# Balancing_Robot_1_1_Sensors.net
KiCad netlist of a schematic drawn in Altium Designer
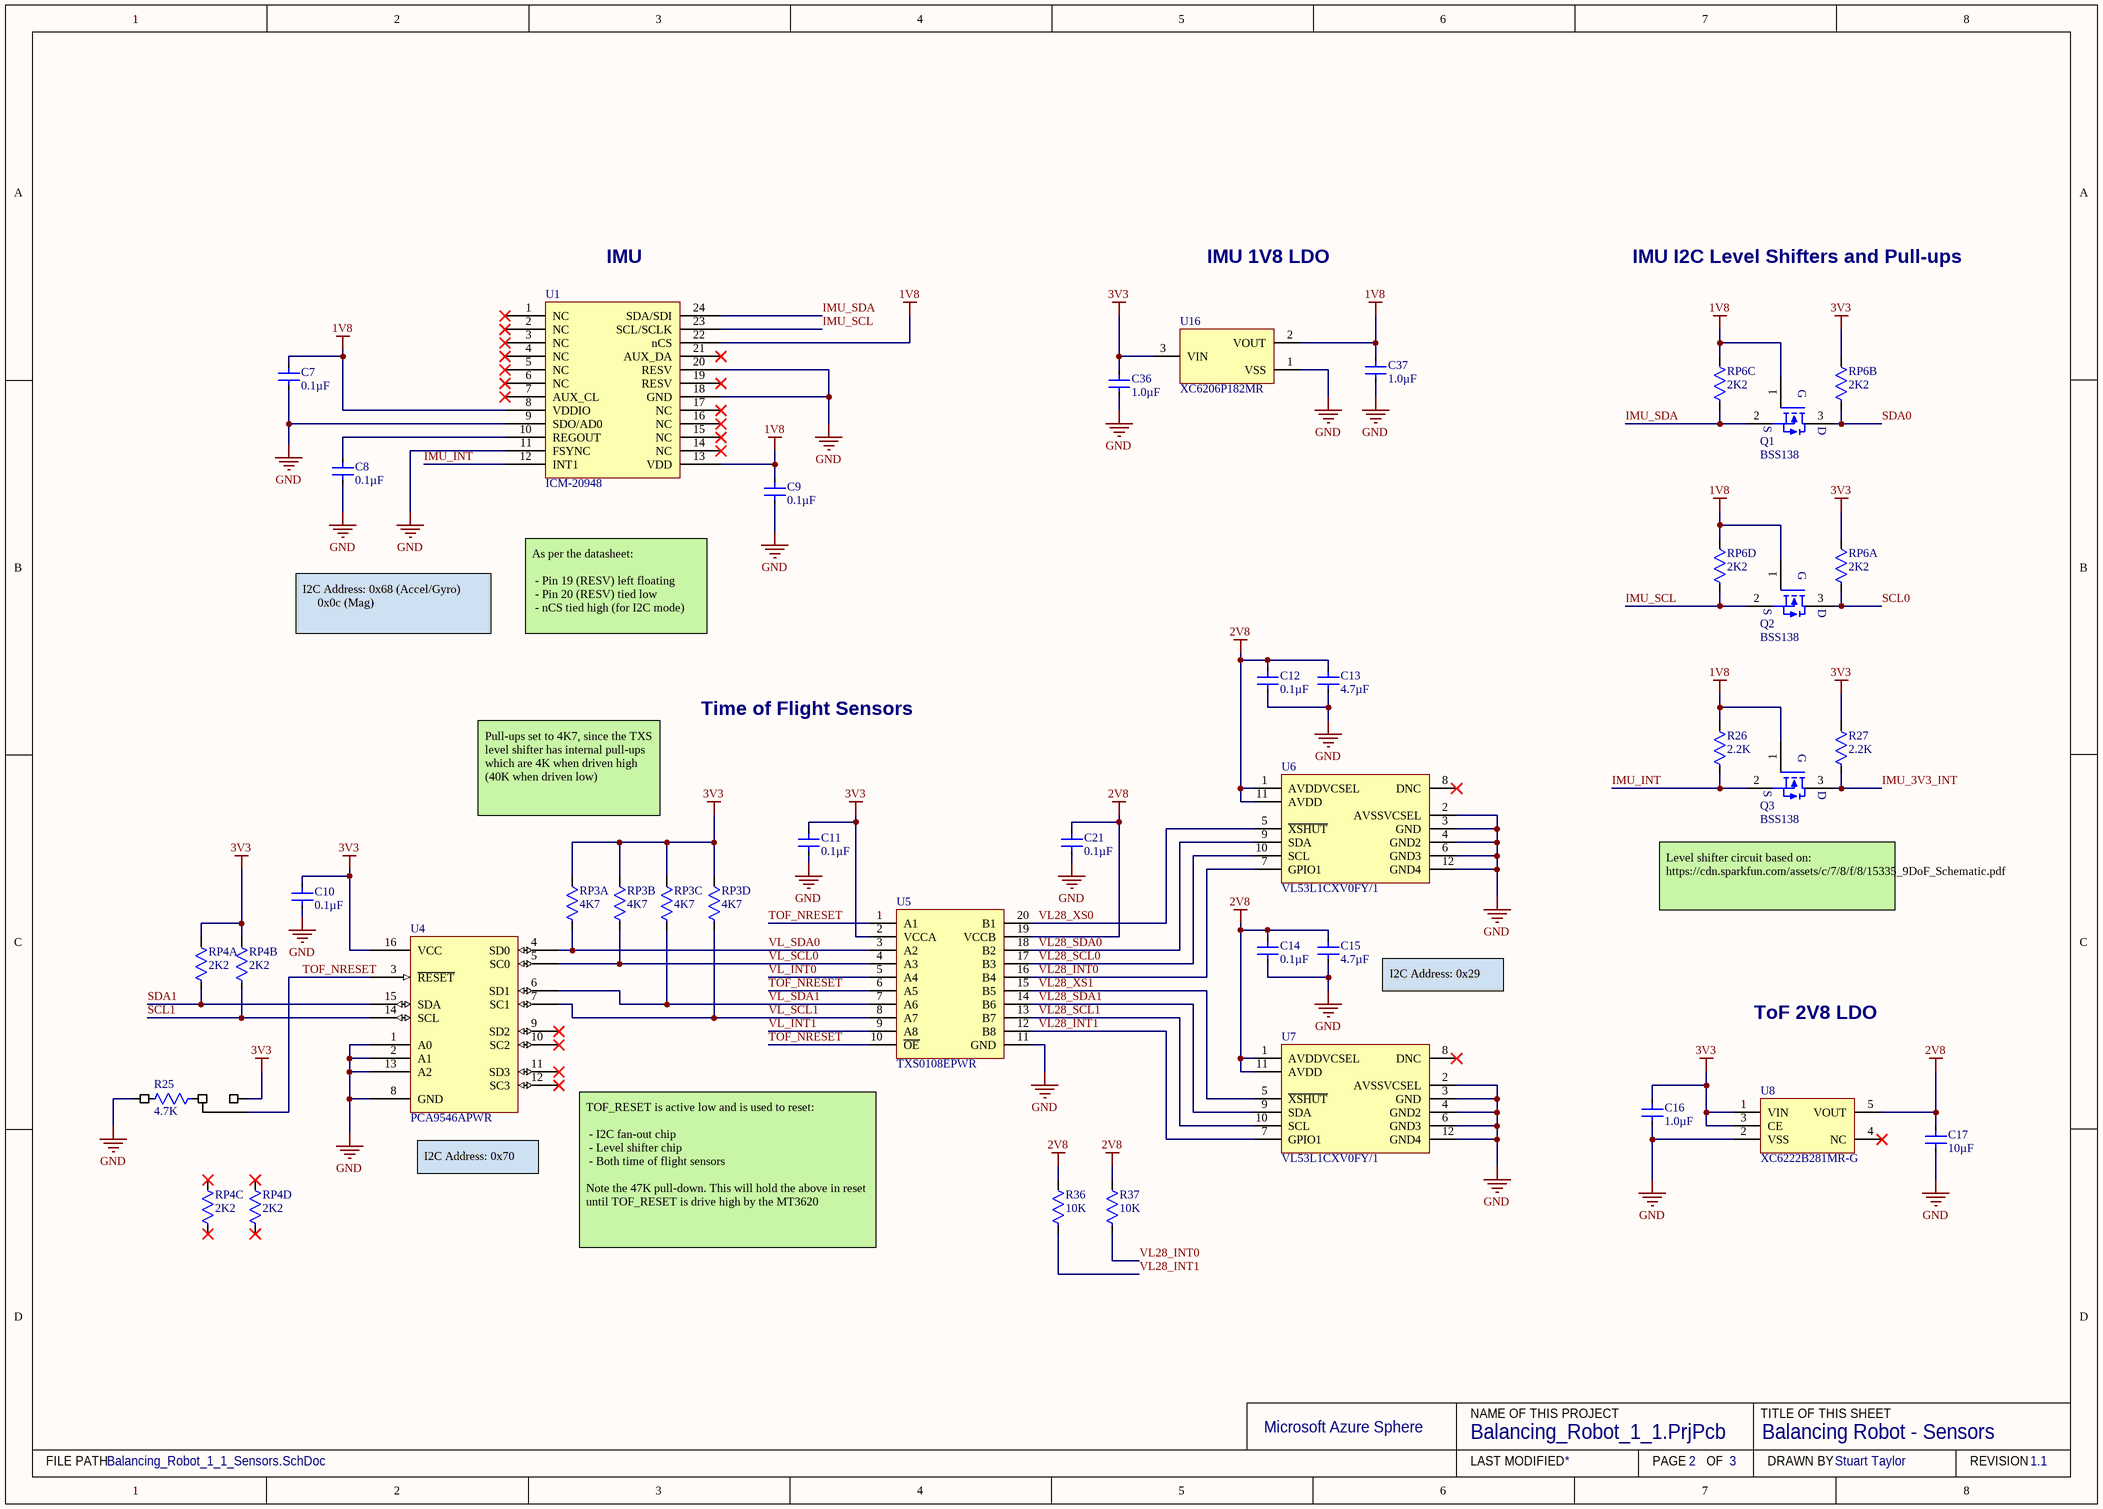
[diagram p0: Balancing_Robot_1_1_Sensors.SchDoc]

(export (version "E")
  (design (tool "Eeschema 10.0.6"))
  (components
    (comp (ref "C7")
      (value "0.1µF")
      (footprint "CAPC1005-EIA0402 0.55MM MED")
      (description "CAP CER 0.1UF 50V 10% X7R 0402")
      (fields
        (field (name "MANUFACTURER") "TDK Corporation")
        (field (name "MANUFACTURER PART NUMBER") "C1005X7R1H104K050BB")
        (field (name "CAPACITANCE") "0.1µF")
      )
      (libsource (lib "TDK_Capacitor_C_0402") (part "0.1µF 0402 X7R 50V"))
    )
    (comp (ref "C8")
      (value "0.1µF")
      (footprint "CAPC1005-EIA0402 0.55MM MED")
      (description "CAP CER 0.1UF 50V 10% X7R 0402")
      (fields
        (field (name "MANUFACTURER") "TDK Corporation")
        (field (name "MANUFACTURER PART NUMBER") "C1005X7R1H104K050BB")
        (field (name "CAPACITANCE") "0.1µF")
      )
      (libsource (lib "TDK_Capacitor_C_0402") (part "0.1µF 0402 X7R 50V"))
    )
    (comp (ref "C9")
      (value "0.1µF")
      (footprint "CAPC1005-EIA0402 0.55MM MED")
      (description "CAP CER 0.1UF 50V 10% X7R 0402")
      (fields
        (field (name "MANUFACTURER") "TDK Corporation")
        (field (name "MANUFACTURER PART NUMBER") "C1005X7R1H104K050BB")
        (field (name "CAPACITANCE") "0.1µF")
      )
      (libsource (lib "TDK_Capacitor_C_0402") (part "0.1µF 0402 X7R 50V"))
    )
    (comp (ref "C10")
      (value "0.1µF")
      (footprint "CAPC1005-EIA0402 0.55MM MED")
      (description "CAP CER 0.1UF 50V 10% X7R 0402")
      (fields
        (field (name "MANUFACTURER") "TDK Corporation")
        (field (name "MANUFACTURER PART NUMBER") "C1005X7R1H104K050BB")
        (field (name "CAPACITANCE") "0.1µF")
      )
      (libsource (lib "TDK_Capacitor_C_0402") (part "0.1µF 0402 X7R 50V"))
    )
    (comp (ref "C11")
      (value "0.1µF")
      (footprint "CAPC1005-EIA0402 0.55MM MED")
      (description "CAP CER 0.1UF 50V 10% X7R 0402")
      (fields
        (field (name "MANUFACTURER") "TDK Corporation")
        (field (name "MANUFACTURER PART NUMBER") "C1005X7R1H104K050BB")
        (field (name "CAPACITANCE") "0.1µF")
      )
      (libsource (lib "TDK_Capacitor_C_0402") (part "0.1µF 0402 X7R 50V"))
    )
    (comp (ref "C12")
      (value "0.1µF")
      (footprint "CAPC1005-EIA0402 0.55MM MED")
      (description "CAP CER 0.1UF 50V 10% X7R 0402")
      (fields
        (field (name "MANUFACTURER") "TDK Corporation")
        (field (name "MANUFACTURER PART NUMBER") "C1005X7R1H104K050BB")
        (field (name "CAPACITANCE") "0.1µF")
      )
      (libsource (lib "TDK_Capacitor_C_0402") (part "0.1µF 0402 X7R 50V"))
    )
    (comp (ref "C13")
      (value "C1005X5R1A475K050BC")
      (footprint "CAPC1005-EIA0402 0.55MM MED")
      (description "CAP CER 4.7UF 10V 10% X5R 0402")
      (fields
        (field (name "MANUFACTURER") "TDK Corporation")
        (field (name "TOLERANCE") "±10%")
        (field (name "CAPACITANCE") "4.7µF")
      )
      (libsource (lib "TDK_Capacitor_C_0402") (part "4.7µF 0402 X5R 10V"))
    )
    (comp (ref "C14")
      (value "0.1µF")
      (footprint "CAPC1005-EIA0402 0.55MM MED")
      (description "CAP CER 0.1UF 50V 10% X7R 0402")
      (fields
        (field (name "MANUFACTURER") "TDK Corporation")
        (field (name "MANUFACTURER PART NUMBER") "C1005X7R1H104K050BB")
        (field (name "CAPACITANCE") "0.1µF")
      )
      (libsource (lib "TDK_Capacitor_C_0402") (part "0.1µF 0402 X7R 50V"))
    )
    (comp (ref "C15")
      (value "C1005X5R1A475K050BC")
      (footprint "CAPC1005-EIA0402 0.55MM MED")
      (description "CAP CER 4.7UF 10V 10% X5R 0402")
      (fields
        (field (name "MANUFACTURER") "TDK Corporation")
        (field (name "TOLERANCE") "±10%")
        (field (name "CAPACITANCE") "4.7µF")
      )
      (libsource (lib "TDK_Capacitor_C_0402") (part "4.7µF 0402 X5R 10V"))
    )
    (comp (ref "C16")
      (value "C1005X5R1V105K050BC")
      (footprint "CAPC1005-EIA0402 0.55MM MED")
      (description "CAP CER 1UF 35V 10% X5R 0402")
      (fields
        (field (name "MANUFACTURER") "TDK Corporation")
        (field (name "TOLERANCE") "±10%")
        (field (name "CAPACITANCE") "1.0µF")
      )
      (libsource (lib "TDK_Capacitor_C_0402") (part "1.0µF 0402 X5R 35V"))
    )
    (comp (ref "C17")
      (value "10µF")
      (footprint "CAPC1005-EIA0402 0.55MM MED")
      (description "CAP CER 10UF 6.3V 20% X5R 0402")
      (fields
        (field (name "MANUFACTURER") "TDK Corporation")
        (field (name "MANUFACTURER PART NUMBER") "C1005X5R0J106M050BC")
        (field (name "CAPACITANCE") "10µF")
      )
      (libsource (lib "TDK_Capacitor_C_0402") (part "10µF 0402 X5R 6.3V"))
    )
    (comp (ref "C21")
      (value "0.1µF")
      (footprint "CAPC1005-EIA0402 0.55MM MED")
      (description "CAP CER 0.1UF 50V 10% X7R 0402")
      (fields
        (field (name "MANUFACTURER") "TDK Corporation")
        (field (name "MANUFACTURER PART NUMBER") "C1005X7R1H104K050BB")
        (field (name "CAPACITANCE") "0.1µF")
      )
      (libsource (lib "TDK_Capacitor_C_0402") (part "0.1µF 0402 X7R 50V"))
    )
    (comp (ref "C36")
      (value "C1005X5R1V105K050BC")
      (footprint "CAPC1005-EIA0402 0.55MM MED")
      (description "CAP CER 1UF 35V 10% X5R 0402")
      (fields
        (field (name "MANUFACTURER") "TDK Corporation")
        (field (name "TOLERANCE") "±10%")
        (field (name "CAPACITANCE") "1.0µF")
      )
      (libsource (lib "TDK_Capacitor_C_0402") (part "1.0µF 0402 X5R 35V"))
    )
    (comp (ref "C37")
      (value "C1005X5R1V105K050BC")
      (footprint "CAPC1005-EIA0402 0.55MM MED")
      (description "CAP CER 1UF 35V 10% X5R 0402")
      (fields
        (field (name "MANUFACTURER") "TDK Corporation")
        (field (name "TOLERANCE") "±10%")
        (field (name "CAPACITANCE") "1.0µF")
      )
      (libsource (lib "TDK_Capacitor_C_0402") (part "1.0µF 0402 X5R 35V"))
    )
    (comp (ref "Q1")
      (value "BSS138")
      (footprint "TOREX-SOT23-3")
      (description "MOSFET N-CH 50V 220MA SOT-23")
      (fields (field (name "MANUFACTURER") "Micross"))
      (libsource (lib "Fairchild") (part "BSS138"))
    )
    (comp (ref "Q2")
      (value "BSS138")
      (footprint "TOREX-SOT23-3")
      (description "MOSFET N-CH 50V 220MA SOT-23")
      (fields (field (name "MANUFACTURER") "Micross"))
      (libsource (lib "Fairchild") (part "BSS138"))
    )
    (comp (ref "Q3")
      (value "BSS138")
      (footprint "TOREX-SOT23-3")
      (description "MOSFET N-CH 50V 220MA SOT-23")
      (fields (field (name "MANUFACTURER") "Micross"))
      (libsource (lib "Fairchild") (part "BSS138"))
    )
    (comp (ref "R25")
      (value "4.7K")
      (footprint "THREE-WAY-0402-NO-SHORT")
      (description "RES SMD 4.7K JUMPER 1/10W 0402")
      (fields
        (field (name "MANUFACTURER") "Panasonic Electronic Components")
        (field (name "MANUFACTURER PART NUMBER") "ERJ-2RKF4701X")
      )
      (libsource (lib "generic-res") (part "THREE-WAY-4K7-0402-NO-SHORT"))
    )
    (comp (ref "R26")
      (value "2.2K")
      (footprint "RES 0402 MEDIUM DENSITY")
      (description "RES 2.2K OHM 1/10W 1% 0402 SMD")
      (fields
        (field (name "MANUFACTURER") "Panasonic Electronic Components")
        (field (name "MANUFACTURER PART NUMBER") "ERJ-2RKF2201X")
        (field (name "RESISTANCE (OHMS)") "2.2K")
      )
      (libsource (lib "Panasonic_Resistor_ERJ2R") (part "2.2K"))
    )
    (comp (ref "R27")
      (value "2.2K")
      (footprint "RES 0402 MEDIUM DENSITY")
      (description "RES 2.2K OHM 1/10W 1% 0402 SMD")
      (fields
        (field (name "MANUFACTURER") "Panasonic Electronic Components")
        (field (name "MANUFACTURER PART NUMBER") "ERJ-2RKF2201X")
        (field (name "RESISTANCE (OHMS)") "2.2K")
      )
      (libsource (lib "Panasonic_Resistor_ERJ2R") (part "2.2K"))
    )
    (comp (ref "R36")
      (value "10K")
      (footprint "RES 0402 MEDIUM DENSITY")
      (description "RES 10K OHM 1/10W 1% 0402 SMD")
      (fields
        (field (name "MANUFACTURER") "Panasonic Electronic Components")
        (field (name "MANUFACTURER PART NUMBER") "ERJ-2RKF1002X")
        (field (name "RESISTANCE (OHMS)") "10K")
      )
      (libsource (lib "Panasonic_Resistor_ERJ2R") (part "10K"))
    )
    (comp (ref "R37")
      (value "10K")
      (footprint "RES 0402 MEDIUM DENSITY")
      (description "RES 10K OHM 1/10W 1% 0402 SMD")
      (fields
        (field (name "MANUFACTURER") "Panasonic Electronic Components")
        (field (name "MANUFACTURER PART NUMBER") "ERJ-2RKF1002X")
        (field (name "RESISTANCE (OHMS)") "10K")
      )
      (libsource (lib "Panasonic_Resistor_ERJ2R") (part "10K"))
    )
    (comp (ref "RP3")
      (value "4K7")
      (footprint "EXB-N8V")
      (fields
        (field (name "MANUFACTURER") "Panasonic / Panasonic ECG")
        (field (name "MANUFACTURER PART NUMBER") "EXB-N8V472JX")
      )
      (libsource (lib "Panasonic") (part "EXB-N8V472JX"))
    )
    (comp (ref "RP4")
      (value "2K2")
      (footprint "EXB-N8V")
      (fields
        (field (name "MANUFACTURER") "Panasonic / Panasonic ECG")
        (field (name "MANUFACTURER PART NUMBER") "EXB-N8V222JX")
      )
      (libsource (lib "Panasonic") (part "EXB-N8V222JX"))
    )
    (comp (ref "RP6")
      (value "2K2")
      (footprint "EXB-N8V")
      (fields
        (field (name "MANUFACTURER") "Panasonic / Panasonic ECG")
        (field (name "MANUFACTURER PART NUMBER") "EXB-N8V222JX")
      )
      (libsource (lib "Panasonic") (part "EXB-N8V222JX"))
    )
    (comp (ref "U1")
      (value "ICM-20948")
      (footprint "ICM_20948")
      (description "9-axis IMU")
      (fields (field (name "MANUFACTURER") "TDK"))
      (libsource (lib "InvenSense") (part "ICM-20948"))
    )
    (comp (ref "U4")
      (value "PCA9546APWR")
      (footprint "PCA9546APWR")
      (fields (field (name "MANUFACTURER") "Texas Instruments"))
      (libsource (lib "TexasInstruments") (part "PCA9546APWR"))
    )
    (comp (ref "U5")
      (value "TXS0108EPWR")
      (footprint "TXS0108EPWR")
      (description "IC 8BIT NON-INV TRANSLTR 20TSSOP")
      (fields (field (name "MANUFACTURER") "Texas Instruments"))
      (libsource (lib "TexasInstruments") (part "TXS0108EPWR"))
    )
    (comp (ref "U6")
      (value "VL53L1CXV0FY/1")
      (footprint "VL53L1X")
      (description "OPTICAL LGA12 4.9X2")
      (fields (field (name "MANUFACTURER") "STMicroelectronics"))
      (libsource (lib "ST") (part "VL53L1CXV0FY/1"))
    )
    (comp (ref "U7")
      (value "VL53L1CXV0FY/1")
      (footprint "VL53L1X")
      (description "OPTICAL LGA12 4.9X2")
      (fields (field (name "MANUFACTURER") "STMicroelectronics"))
      (libsource (lib "ST") (part "VL53L1CXV0FY/1"))
    )
    (comp (ref "U8")
      (value "XC6222B281MR-G")
      (footprint "SOT25")
      (description "Reverse Current Protection, 700mA High Speed LDO Regulator")
      (fields (field (name "MANUFACTURER") "Torex"))
      (libsource (lib "Torex") (part "XC6222B281MR-G"))
    )
    (comp (ref "U16")
      (value "XC6206P182MR")
      (footprint "TOREX-SOT23-3")
      (fields (field (name "MANUFACTURER") "Torex Semiconductor"))
      (libsource (lib "Torex") (part "XC6206P182MR"))
    )
  )
  (nets
    (net (code "1") (name "/IMU_3V3_INT") (class "Default")
      (node (ref "Q3") (pin "3") (pinfunction "D_3") (pintype "passive"))
      (node (ref "R27") (pin "2") (pinfunction "2_2") (pintype "passive"))
    )
    (net (code "2") (name "/IMU_INT") (class "Default")
      (node (ref "Q3") (pin "2") (pinfunction "S_2") (pintype "passive"))
      (node (ref "R26") (pin "2") (pinfunction "2_2") (pintype "passive"))
      (node (ref "U1") (pin "12") (pinfunction "INT1_12") (pintype "passive"))
    )
    (net (code "3") (name "/IMU_SCL") (class "Default")
      (node (ref "Q2") (pin "2") (pinfunction "S_2") (pintype "passive"))
      (node (ref "RP6") (pin "7") (pinfunction "7_7") (pintype "passive"))
      (node (ref "U1") (pin "23") (pinfunction "SCL/SCLK_23") (pintype "passive"))
    )
    (net (code "4") (name "/IMU_SDA") (class "Default")
      (node (ref "Q1") (pin "2") (pinfunction "S_2") (pintype "passive"))
      (node (ref "RP6") (pin "5") (pinfunction "5_5") (pintype "passive"))
      (node (ref "U1") (pin "24") (pinfunction "SDA/SDI_24") (pintype "passive"))
    )
    (net (code "5") (name "/SCL0") (class "Default")
      (node (ref "Q2") (pin "3") (pinfunction "D_3") (pintype "passive"))
      (node (ref "RP6") (pin "1") (pinfunction "1_1") (pintype "passive"))
    )
    (net (code "6") (name "/SCL1") (class "Default")
      (node (ref "RP4") (pin "3") (pinfunction "3_3") (pintype "passive"))
      (node (ref "U4") (pin "14") (pinfunction "SCL_14") (pintype "bidirectional"))
    )
    (net (code "7") (name "/SDA0") (class "Default")
      (node (ref "Q1") (pin "3") (pinfunction "D_3") (pintype "passive"))
      (node (ref "RP6") (pin "3") (pinfunction "3_3") (pintype "passive"))
    )
    (net (code "8") (name "/SDA1") (class "Default")
      (node (ref "RP4") (pin "1") (pinfunction "1_1") (pintype "passive"))
      (node (ref "U4") (pin "15") (pinfunction "SDA_15") (pintype "bidirectional"))
    )
    (net (code "9") (name "/TOF_NRESET") (class "Default")
      (node (ref "R25") (pin "2") (pinfunction "2_2") (pintype "passive"))
      (node (ref "U4") (pin "3") (pinfunction "~{RESET}_3") (pintype "input"))
      (node (ref "U5") (pin "1") (pinfunction "A1_1") (pintype "passive"))
      (node (ref "U5") (pin "10") (pinfunction "~{OE}_10") (pintype "passive"))
      (node (ref "U5") (pin "6") (pinfunction "A5_6") (pintype "passive"))
    )
    (net (code "10") (name "/VL28_INT0") (class "Default")
      (node (ref "R37") (pin "2") (pinfunction "2_2") (pintype "passive"))
      (node (ref "U5") (pin "16") (pinfunction "B4_16") (pintype "passive"))
      (node (ref "U6") (pin "7") (pinfunction "GPIO1_7") (pintype "passive"))
    )
    (net (code "11") (name "/VL28_INT1") (class "Default")
      (node (ref "R36") (pin "2") (pinfunction "2_2") (pintype "passive"))
      (node (ref "U5") (pin "12") (pinfunction "B8_12") (pintype "passive"))
      (node (ref "U7") (pin "7") (pinfunction "GPIO1_7") (pintype "passive"))
    )
    (net (code "12") (name "/VL28_SCL0") (class "Default")
      (node (ref "U5") (pin "17") (pinfunction "B3_17") (pintype "passive"))
      (node (ref "U6") (pin "10") (pinfunction "SCL_10") (pintype "passive"))
    )
    (net (code "13") (name "/VL28_SCL1") (class "Default")
      (node (ref "U5") (pin "13") (pinfunction "B7_13") (pintype "passive"))
      (node (ref "U7") (pin "10") (pinfunction "SCL_10") (pintype "passive"))
    )
    (net (code "14") (name "/VL28_SDA0") (class "Default")
      (node (ref "U5") (pin "18") (pinfunction "B2_18") (pintype "passive"))
      (node (ref "U6") (pin "9") (pinfunction "SDA_9") (pintype "passive"))
    )
    (net (code "15") (name "/VL28_SDA1") (class "Default")
      (node (ref "U5") (pin "14") (pinfunction "B6_14") (pintype "passive"))
      (node (ref "U7") (pin "9") (pinfunction "SDA_9") (pintype "passive"))
    )
    (net (code "16") (name "/VL28_XS0") (class "Default")
      (node (ref "U5") (pin "20") (pinfunction "B1_20") (pintype "passive"))
      (node (ref "U6") (pin "5") (pinfunction "~{XSHUT}_5") (pintype "passive"))
    )
    (net (code "17") (name "/VL28_XS1") (class "Default")
      (node (ref "U5") (pin "15") (pinfunction "B5_15") (pintype "passive"))
      (node (ref "U7") (pin "5") (pinfunction "~{XSHUT}_5") (pintype "passive"))
    )
    (net (code "18") (name "/VL_INT0") (class "Default")
      (node (ref "U5") (pin "5") (pinfunction "A4_5") (pintype "passive"))
    )
    (net (code "19") (name "/VL_INT1") (class "Default")
      (node (ref "U5") (pin "9") (pinfunction "A8_9") (pintype "passive"))
    )
    (net (code "20") (name "/VL_SCL0") (class "Default")
      (node (ref "RP3") (pin "3") (pinfunction "3_3") (pintype "passive"))
      (node (ref "U4") (pin "5") (pinfunction "SC0_5") (pintype "bidirectional"))
      (node (ref "U5") (pin "4") (pinfunction "A3_4") (pintype "passive"))
    )
    (net (code "21") (name "/VL_SCL1") (class "Default")
      (node (ref "RP3") (pin "7") (pinfunction "7_7") (pintype "passive"))
      (node (ref "U4") (pin "7") (pinfunction "SC1_7") (pintype "bidirectional"))
      (node (ref "U5") (pin "8") (pinfunction "A7_8") (pintype "passive"))
    )
    (net (code "22") (name "/VL_SDA0") (class "Default")
      (node (ref "RP3") (pin "1") (pinfunction "1_1") (pintype "passive"))
      (node (ref "U4") (pin "4") (pinfunction "SD0_4") (pintype "bidirectional"))
      (node (ref "U5") (pin "3") (pinfunction "A2_3") (pintype "passive"))
    )
    (net (code "23") (name "/VL_SDA1") (class "Default")
      (node (ref "RP3") (pin "5") (pinfunction "5_5") (pintype "passive"))
      (node (ref "U4") (pin "6") (pinfunction "SD1_6") (pintype "bidirectional"))
      (node (ref "U5") (pin "7") (pinfunction "A6_7") (pintype "passive"))
    )
    (net (code "24") (name "1V8") (class "Default")
      (node (ref "C37") (pin "2") (pinfunction "2_2") (pintype "passive"))
      (node (ref "C7") (pin "2") (pinfunction "2_2") (pintype "passive"))
      (node (ref "C9") (pin "2") (pinfunction "2_2") (pintype "passive"))
      (node (ref "Q1") (pin "1") (pinfunction "G_1") (pintype "passive"))
      (node (ref "Q2") (pin "1") (pinfunction "G_1") (pintype "passive"))
      (node (ref "Q3") (pin "1") (pinfunction "G_1") (pintype "passive"))
      (node (ref "R26") (pin "1") (pinfunction "1_1") (pintype "passive"))
      (node (ref "RP6") (pin "6") (pinfunction "6_6") (pintype "passive"))
      (node (ref "RP6") (pin "8") (pinfunction "8_8") (pintype "passive"))
      (node (ref "U1") (pin "13") (pinfunction "VDD_13") (pintype "passive"))
      (node (ref "U1") (pin "22") (pinfunction "nCS_22") (pintype "passive"))
      (node (ref "U1") (pin "8") (pinfunction "VDDIO_8") (pintype "passive"))
      (node (ref "U16") (pin "2") (pinfunction "VOUT_2") (pintype "passive"))
    )
    (net (code "25") (name "2V8") (class "Default")
      (node (ref "C12") (pin "2") (pinfunction "2_2") (pintype "passive"))
      (node (ref "C13") (pin "2") (pinfunction "2_2") (pintype "passive"))
      (node (ref "C14") (pin "2") (pinfunction "2_2") (pintype "passive"))
      (node (ref "C15") (pin "2") (pinfunction "2_2") (pintype "passive"))
      (node (ref "C17") (pin "2") (pinfunction "2_2") (pintype "passive"))
      (node (ref "C21") (pin "2") (pinfunction "2_2") (pintype "passive"))
      (node (ref "R36") (pin "1") (pinfunction "1_1") (pintype "passive"))
      (node (ref "R37") (pin "1") (pinfunction "1_1") (pintype "passive"))
      (node (ref "U5") (pin "19") (pinfunction "VCCB_19") (pintype "passive"))
      (node (ref "U6") (pin "1") (pinfunction "AVDDVCSEL_1") (pintype "passive"))
      (node (ref "U6") (pin "11") (pinfunction "AVDD_11") (pintype "passive"))
      (node (ref "U7") (pin "1") (pinfunction "AVDDVCSEL_1") (pintype "passive"))
      (node (ref "U7") (pin "11") (pinfunction "AVDD_11") (pintype "passive"))
      (node (ref "U8") (pin "5") (pinfunction "VOUT_5") (pintype "passive"))
    )
    (net (code "26") (name "3V3") (class "Default")
      (node (ref "C10") (pin "2") (pinfunction "2_2") (pintype "passive"))
      (node (ref "C11") (pin "2") (pinfunction "2_2") (pintype "passive"))
      (node (ref "C16") (pin "2") (pinfunction "2_2") (pintype "passive"))
      (node (ref "C36") (pin "2") (pinfunction "2_2") (pintype "passive"))
      (node (ref "R25") (pin "3") (pinfunction "3_3") (pintype "passive"))
      (node (ref "R27") (pin "1") (pinfunction "1_1") (pintype "passive"))
      (node (ref "RP3") (pin "2") (pinfunction "2_2") (pintype "passive"))
      (node (ref "RP3") (pin "4") (pinfunction "4_4") (pintype "passive"))
      (node (ref "RP3") (pin "6") (pinfunction "6_6") (pintype "passive"))
      (node (ref "RP3") (pin "8") (pinfunction "8_8") (pintype "passive"))
      (node (ref "RP4") (pin "2") (pinfunction "2_2") (pintype "passive"))
      (node (ref "RP4") (pin "4") (pinfunction "4_4") (pintype "passive"))
      (node (ref "RP6") (pin "2") (pinfunction "2_2") (pintype "passive"))
      (node (ref "RP6") (pin "4") (pinfunction "4_4") (pintype "passive"))
      (node (ref "U16") (pin "3") (pinfunction "VIN_3") (pintype "passive"))
      (node (ref "U4") (pin "16") (pinfunction "VCC_16") (pintype "power_in"))
      (node (ref "U5") (pin "2") (pinfunction "VCCA_2") (pintype "passive"))
      (node (ref "U8") (pin "1") (pinfunction "VIN_1") (pintype "passive"))
      (node (ref "U8") (pin "3") (pinfunction "CE_3") (pintype "passive"))
    )
    (net (code "27") (name "GND") (class "Default")
      (node (ref "C10") (pin "1") (pinfunction "1_1") (pintype "passive"))
      (node (ref "C11") (pin "1") (pinfunction "1_1") (pintype "passive"))
      (node (ref "C12") (pin "1") (pinfunction "1_1") (pintype "passive"))
      (node (ref "C13") (pin "1") (pinfunction "1_1") (pintype "passive"))
      (node (ref "C14") (pin "1") (pinfunction "1_1") (pintype "passive"))
      (node (ref "C15") (pin "1") (pinfunction "1_1") (pintype "passive"))
      (node (ref "C16") (pin "1") (pinfunction "1_1") (pintype "passive"))
      (node (ref "C17") (pin "1") (pinfunction "1_1") (pintype "passive"))
      (node (ref "C21") (pin "1") (pinfunction "1_1") (pintype "passive"))
      (node (ref "C36") (pin "1") (pinfunction "1_1") (pintype "passive"))
      (node (ref "C37") (pin "1") (pinfunction "1_1") (pintype "passive"))
      (node (ref "C7") (pin "1") (pinfunction "1_1") (pintype "passive"))
      (node (ref "C8") (pin "1") (pinfunction "1_1") (pintype "passive"))
      (node (ref "C9") (pin "1") (pinfunction "1_1") (pintype "passive"))
      (node (ref "R25") (pin "1") (pinfunction "1_1") (pintype "passive"))
      (node (ref "U1") (pin "11") (pinfunction "FSYNC_11") (pintype "passive"))
      (node (ref "U1") (pin "18") (pinfunction "GND_18") (pintype "passive"))
      (node (ref "U1") (pin "20") (pinfunction "RESV_20") (pintype "passive"))
      (node (ref "U1") (pin "9") (pinfunction "SDO/AD0_9") (pintype "passive"))
      (node (ref "U16") (pin "1") (pinfunction "VSS_1") (pintype "passive"))
      (node (ref "U4") (pin "1") (pinfunction "A0_1") (pintype "power_in"))
      (node (ref "U4") (pin "13") (pinfunction "A2_13") (pintype "power_in"))
      (node (ref "U4") (pin "2") (pinfunction "A1_2") (pintype "power_in"))
      (node (ref "U4") (pin "8") (pinfunction "GND_8") (pintype "power_in"))
      (node (ref "U5") (pin "11") (pinfunction "GND_11") (pintype "passive"))
      (node (ref "U6") (pin "12") (pinfunction "GND4_12") (pintype "passive"))
      (node (ref "U6") (pin "2") (pinfunction "AVSSVCSEL_2") (pintype "passive"))
      (node (ref "U6") (pin "3") (pinfunction "GND_3") (pintype "passive"))
      (node (ref "U6") (pin "4") (pinfunction "GND2_4") (pintype "passive"))
      (node (ref "U6") (pin "6") (pinfunction "GND3_6") (pintype "passive"))
      (node (ref "U7") (pin "12") (pinfunction "GND4_12") (pintype "passive"))
      (node (ref "U7") (pin "2") (pinfunction "AVSSVCSEL_2") (pintype "passive"))
      (node (ref "U7") (pin "3") (pinfunction "GND_3") (pintype "passive"))
      (node (ref "U7") (pin "4") (pinfunction "GND2_4") (pintype "passive"))
      (node (ref "U7") (pin "6") (pinfunction "GND3_6") (pintype "passive"))
      (node (ref "U8") (pin "2") (pinfunction "VSS_2") (pintype "passive"))
    )
    (net (code "28") (name "Net-(U1-REGOUT)") (class "Default")
      (node (ref "C8") (pin "2") (pinfunction "2_2") (pintype "passive"))
      (node (ref "U1") (pin "10") (pinfunction "REGOUT_10") (pintype "passive"))
    )
    (net (code "29") (name "unconnected-(RP4-Pad5)") (class "Default")
      (node (ref "RP4") (pin "5") (pinfunction "5_5") (pintype "passive+no_connect"))
    )
    (net (code "30") (name "unconnected-(RP4-Pad6)") (class "Default")
      (node (ref "RP4") (pin "6") (pinfunction "6_6") (pintype "passive+no_connect"))
    )
    (net (code "31") (name "unconnected-(RP4-Pad7)") (class "Default")
      (node (ref "RP4") (pin "7") (pinfunction "7_7") (pintype "passive+no_connect"))
    )
    (net (code "32") (name "unconnected-(RP4-Pad8)") (class "Default")
      (node (ref "RP4") (pin "8") (pinfunction "8_8") (pintype "passive+no_connect"))
    )
    (net (code "33") (name "unconnected-(U1-AUX_CL-Pad7)") (class "Default")
      (node (ref "U1") (pin "7") (pinfunction "AUX_CL_7") (pintype "passive+no_connect"))
    )
    (net (code "34") (name "unconnected-(U1-AUX_DA-Pad21)") (class "Default")
      (node (ref "U1") (pin "21") (pinfunction "AUX_DA_21") (pintype "passive+no_connect"))
    )
    (net (code "35") (name "unconnected-(U1-NC-Pad1)") (class "Default")
      (node (ref "U1") (pin "1") (pinfunction "NC_1") (pintype "passive+no_connect"))
    )
    (net (code "36") (name "unconnected-(U1-NC-Pad2)") (class "Default")
      (node (ref "U1") (pin "2") (pinfunction "NC_2") (pintype "passive+no_connect"))
    )
    (net (code "37") (name "unconnected-(U1-NC-Pad3)") (class "Default")
      (node (ref "U1") (pin "3") (pinfunction "NC_3") (pintype "passive+no_connect"))
    )
    (net (code "38") (name "unconnected-(U1-NC-Pad4)") (class "Default")
      (node (ref "U1") (pin "4") (pinfunction "NC_4") (pintype "passive+no_connect"))
    )
    (net (code "39") (name "unconnected-(U1-NC-Pad5)") (class "Default")
      (node (ref "U1") (pin "5") (pinfunction "NC_5") (pintype "passive+no_connect"))
    )
    (net (code "40") (name "unconnected-(U1-NC-Pad6)") (class "Default")
      (node (ref "U1") (pin "6") (pinfunction "NC_6") (pintype "passive+no_connect"))
    )
    (net (code "41") (name "unconnected-(U1-NC-Pad14)") (class "Default")
      (node (ref "U1") (pin "14") (pinfunction "NC_14") (pintype "passive+no_connect"))
    )
    (net (code "42") (name "unconnected-(U1-NC-Pad15)") (class "Default")
      (node (ref "U1") (pin "15") (pinfunction "NC_15") (pintype "passive+no_connect"))
    )
    (net (code "43") (name "unconnected-(U1-NC-Pad16)") (class "Default")
      (node (ref "U1") (pin "16") (pinfunction "NC_16") (pintype "passive+no_connect"))
    )
    (net (code "44") (name "unconnected-(U1-NC-Pad17)") (class "Default")
      (node (ref "U1") (pin "17") (pinfunction "NC_17") (pintype "passive+no_connect"))
    )
    (net (code "45") (name "unconnected-(U1-RESV-Pad19)") (class "Default")
      (node (ref "U1") (pin "19") (pinfunction "RESV_19") (pintype "passive+no_connect"))
    )
    (net (code "46") (name "unconnected-(U4-SC2-Pad10)") (class "Default")
      (node (ref "U4") (pin "10") (pinfunction "SC2_10") (pintype "bidirectional+no_connect"))
    )
    (net (code "47") (name "unconnected-(U4-SC3-Pad12)") (class "Default")
      (node (ref "U4") (pin "12") (pinfunction "SC3_12") (pintype "bidirectional+no_connect"))
    )
    (net (code "48") (name "unconnected-(U4-SD2-Pad9)") (class "Default")
      (node (ref "U4") (pin "9") (pinfunction "SD2_9") (pintype "bidirectional+no_connect"))
    )
    (net (code "49") (name "unconnected-(U4-SD3-Pad11)") (class "Default")
      (node (ref "U4") (pin "11") (pinfunction "SD3_11") (pintype "bidirectional+no_connect"))
    )
    (net (code "50") (name "unconnected-(U6-DNC-Pad8)") (class "Default")
      (node (ref "U6") (pin "8") (pinfunction "DNC_8") (pintype "passive+no_connect"))
    )
    (net (code "51") (name "unconnected-(U7-DNC-Pad8)") (class "Default")
      (node (ref "U7") (pin "8") (pinfunction "DNC_8") (pintype "passive+no_connect"))
    )
    (net (code "52") (name "unconnected-(U8-NC-Pad4)") (class "Default")
      (node (ref "U8") (pin "4") (pinfunction "NC_4") (pintype "passive+no_connect"))
    )
  )
)
